# monostable.net
KiCad netlist of a schematic drawn in EAGLE
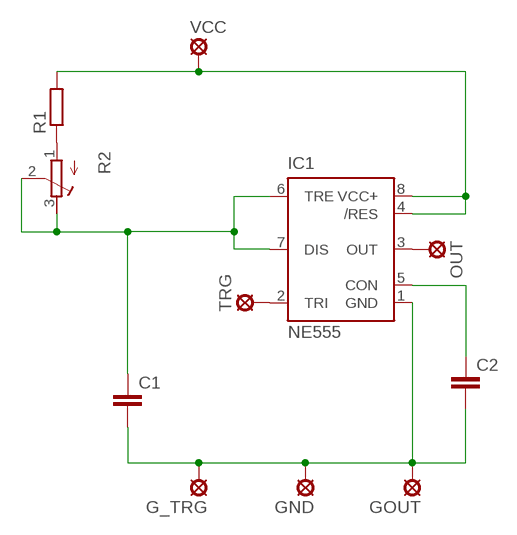
[diagram p0: schematic, sheet 1]

(export (version "E")
  (design (tool "Eeschema 10.0.6"))
  (components
    (comp (ref "C1")
      (value "C-EU050-024X044")
      (footprint "eagle-import:C050-024X044")
      (libsource (lib "eagle-import") (part "C-EU050-024X044"))
    )
    (comp (ref "C2")
      (value "C-EU050-024X044")
      (footprint "eagle-import:C050-024X044")
      (libsource (lib "eagle-import") (part "C-EU050-024X044"))
    )
    (comp (ref "GND")
      (value "LSP10")
      (footprint "eagle-import:LSP10")
      (libsource (lib "eagle-import") (part "LSP10"))
    )
    (comp (ref "GOUT")
      (value "LSP10")
      (footprint "eagle-import:LSP10")
      (libsource (lib "eagle-import") (part "LSP10"))
    )
    (comp (ref "G_TRG")
      (value "LSP10")
      (footprint "eagle-import:LSP10")
      (libsource (lib "eagle-import") (part "LSP10"))
    )
    (comp (ref "IC1")
      (value "NE555")
      (footprint "eagle-import:DIL-08")
      (fields (field (name "MF") "Arrow Electronics") (field (name "MPN") "NE555N"))
      (libsource (lib "eagle-import") (part "NE555"))
    )
    (comp (ref "OUT")
      (value "LSP10")
      (footprint "eagle-import:LSP10")
      (libsource (lib "eagle-import") (part "LSP10"))
    )
    (comp (ref "R1")
      (value "R-EU_0207/10")
      (footprint "eagle-import:0207_10")
      (libsource (lib "eagle-import") (part "R-EU_0207/10"))
    )
    (comp (ref "R2")
      (value "R-TRIMM3339P")
      (footprint "eagle-import:RTRIM3339P")
      (libsource (lib "eagle-import") (part "R-TRIMM3339P"))
    )
    (comp (ref "TRG")
      (value "LSP10")
      (footprint "eagle-import:LSP10")
      (libsource (lib "eagle-import") (part "LSP10"))
    )
    (comp (ref "VCC")
      (value "LSP10")
      (footprint "eagle-import:LSP10")
      (libsource (lib "eagle-import") (part "LSP10"))
    )
  )
  (nets
    (net (code "1") (name "Net-(IC1-CON)") (class "Default")
      (node (ref "C2") (pin "1") (pinfunction "1_1") (pintype "passive"))
      (node (ref "IC1") (pin "5") (pinfunction "CON_5") (pintype "input"))
    )
    (net (code "2") (name "Net-(IC1-DIS)") (class "Default")
      (node (ref "C1") (pin "1") (pinfunction "1_1") (pintype "passive"))
      (node (ref "IC1") (pin "6") (pinfunction "TRE_6") (pintype "input"))
      (node (ref "IC1") (pin "7") (pinfunction "DIS_7") (pintype "input"))
      (node (ref "R2") (pin "2") (pinfunction "S_2") (pintype "passive"))
      (node (ref "R2") (pin "3") (pinfunction "E_3") (pintype "passive"))
    )
    (net (code "3") (name "Net-(IC1-GND)") (class "Default")
      (node (ref "C1") (pin "2") (pinfunction "2_2") (pintype "passive"))
      (node (ref "C2") (pin "2") (pinfunction "2_2") (pintype "passive"))
      (node (ref "GND") (pin "MP") (pinfunction "MP_MP") (pintype "passive"))
      (node (ref "GOUT") (pin "MP") (pinfunction "MP_MP") (pintype "passive"))
      (node (ref "G_TRG") (pin "MP") (pinfunction "MP_MP") (pintype "passive"))
      (node (ref "IC1") (pin "1") (pinfunction "GND_1") (pintype "power_in"))
    )
    (net (code "4") (name "Net-(IC1-OUT)") (class "Default")
      (node (ref "IC1") (pin "3") (pinfunction "OUT_3") (pintype "output"))
      (node (ref "OUT") (pin "MP") (pinfunction "MP_MP") (pintype "passive"))
    )
    (net (code "5") (name "Net-(IC1-TRI)") (class "Default")
      (node (ref "IC1") (pin "2") (pinfunction "TRI_2") (pintype "input"))
      (node (ref "TRG") (pin "MP") (pinfunction "MP_MP") (pintype "passive"))
    )
    (net (code "6") (name "Net-(IC1-VCC+)") (class "Default")
      (node (ref "IC1") (pin "4") (pinfunction "/RES_4") (pintype "input"))
      (node (ref "IC1") (pin "8") (pinfunction "VCC+_8") (pintype "power_in"))
      (node (ref "R1") (pin "2") (pinfunction "2_2") (pintype "passive"))
      (node (ref "VCC") (pin "MP") (pinfunction "MP_MP") (pintype "passive"))
    )
    (net (code "7") (name "Net-(R2-A)") (class "Default")
      (node (ref "R1") (pin "1") (pinfunction "1_1") (pintype "passive"))
      (node (ref "R2") (pin "1") (pinfunction "A_1") (pintype "passive"))
    )
  )
)
